# ToneGeneratorSMD_V2.net
KiCad netlist of a schematic drawn in EAGLE
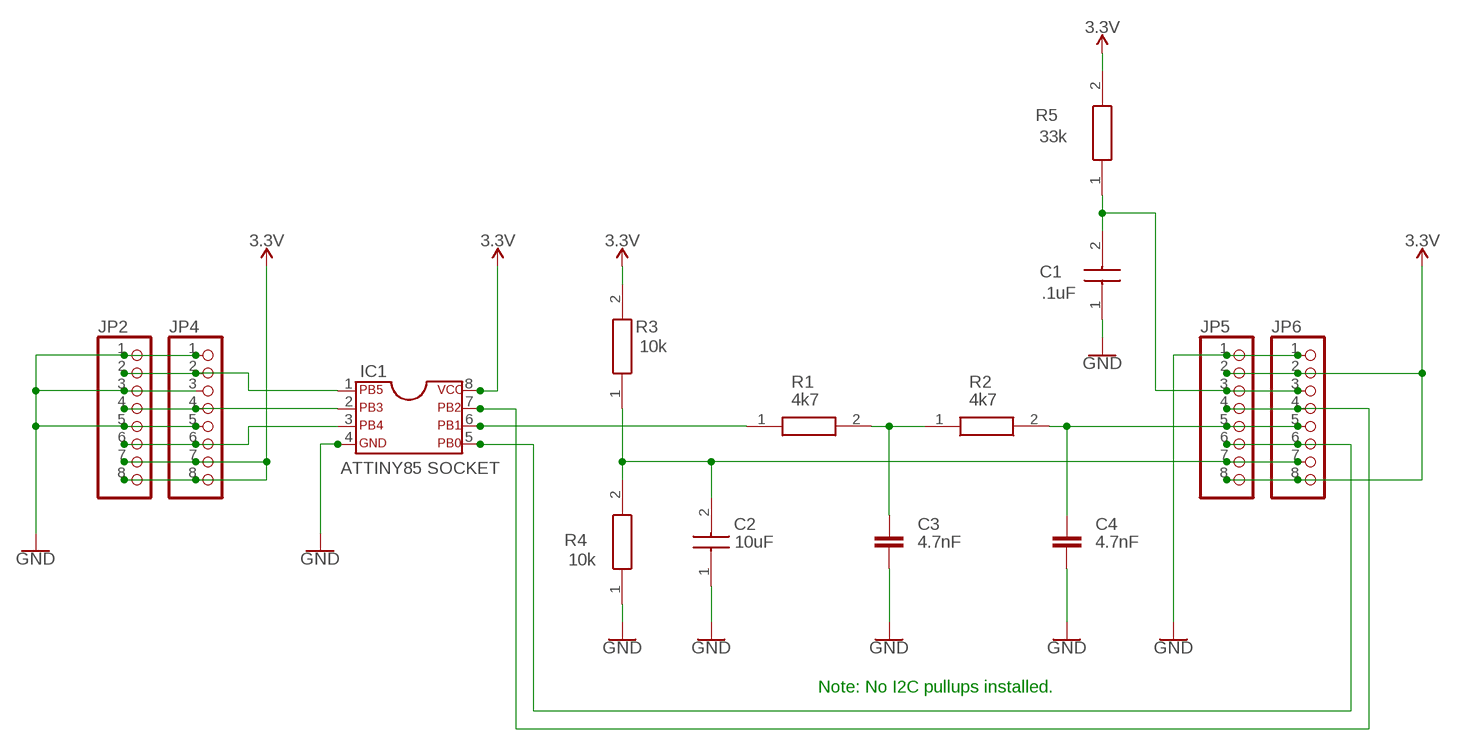
[diagram p0: schematic, sheet 1]

(export (version "E")
  (design (tool "Eeschema 10.0.6"))
  (components
    (comp (ref "C1")
      (value ".1uF")
      (footprint "eagle-import:CAPC2012X90N")
      (fields
        (field (name "MANUFACTURER_PART_NUMBER") "885012207098")
        (field (name "MOUSER_PART_NUMBER") "710-885012207098")
      )
      (libsource (lib "eagle-import") (part "885012207098"))
    )
    (comp (ref "C2")
      (value "10uF")
      (footprint "eagle-import:CAPC2012X145N")
      (fields
        (field (name "MANUFACTURER_PART_NUMBER") "GRM21BR61E106MA73L")
        (field (name "MOUSER_PART_NUMBER") "81-GRM21BR61E106MA3L")
      )
      (libsource (lib "eagle-import") (part "GRM21BR61E106MA73L"))
    )
    (comp (ref "C3")
      (value "4.7nF")
      (footprint "eagle-import:C0805")
      (libsource (lib "eagle-import") (part "C-EUC0805"))
    )
    (comp (ref "C4")
      (value "4.7nF")
      (footprint "eagle-import:C0805")
      (libsource (lib "eagle-import") (part "C-EUC0805"))
    )
    (comp (ref "IC1")
      (value "ATTINY85 SOCKET")
      (footprint "eagle-import:DIL08ATTINY85")
      (libsource (lib "eagle-import") (part "DIL8ATTINY85"))
    )
    (comp (ref "JP2")
      (value "PINHD-1X8")
      (footprint "eagle-import:1X08")
      (libsource (lib "eagle-import") (part "PINHD-1X8"))
    )
    (comp (ref "JP4")
      (value "PINHD-1X8")
      (footprint "eagle-import:1X08")
      (libsource (lib "eagle-import") (part "PINHD-1X8"))
    )
    (comp (ref "JP5")
      (value "PINHD-1X8")
      (footprint "eagle-import:1X08")
      (libsource (lib "eagle-import") (part "PINHD-1X8"))
    )
    (comp (ref "JP6")
      (value "PINHD-1X8")
      (footprint "eagle-import:1X08")
      (libsource (lib "eagle-import") (part "PINHD-1X8"))
    )
    (comp (ref "R1")
      (value "4k7")
      (footprint "eagle-import:RESC2013X65N")
      (fields
        (field (name "MANUFACTURER_PART_NUMBER") "ERJ-6GEYJ472V")
        (field (name "MOUSER_PART_NUMBER") "667-ERJ-6GEYJ472V")
      )
      (libsource (lib "eagle-import") (part "ERJ-6GEYJ472V"))
    )
    (comp (ref "R2")
      (value "4k7")
      (footprint "eagle-import:RESC2013X65N")
      (fields
        (field (name "MANUFACTURER_PART_NUMBER") "ERJ-6GEYJ472V")
        (field (name "MOUSER_PART_NUMBER") "667-ERJ-6GEYJ472V")
      )
      (libsource (lib "eagle-import") (part "ERJ-6GEYJ472V"))
    )
    (comp (ref "R3")
      (value "10k")
      (footprint "eagle-import:RESC2013X65N")
      (fields
        (field (name "MANUFACTURER_PART_NUMBER") "ERJ-6GEYJ472V")
        (field (name "MOUSER_PART_NUMBER") "667-ERJ-6GEYJ472V")
      )
      (libsource (lib "eagle-import") (part "ERJ-6GEYJ472V"))
    )
    (comp (ref "R4")
      (value "10k")
      (footprint "eagle-import:RESC2013X65N")
      (fields
        (field (name "MANUFACTURER_PART_NUMBER") "ERJ-6GEYJ472V")
        (field (name "MOUSER_PART_NUMBER") "667-ERJ-6GEYJ472V")
      )
      (libsource (lib "eagle-import") (part "ERJ-6GEYJ472V"))
    )
    (comp (ref "R5")
      (value "33k")
      (footprint "eagle-import:RESC2013X65N")
      (fields
        (field (name "MANUFACTURER_PART_NUMBER") "ERJ-6GEYJ472V")
        (field (name "MOUSER_PART_NUMBER") "667-ERJ-6GEYJ472V")
      )
      (libsource (lib "eagle-import") (part "ERJ-6GEYJ472V"))
    )
  )
  (nets
    (net (code "1") (name "3.3V") (class "Default")
      (node (ref "IC1") (pin "8") (pinfunction "8_8") (pintype "passive"))
      (node (ref "JP2") (pin "7") (pinfunction "7_7") (pintype "passive"))
      (node (ref "JP2") (pin "8") (pinfunction "8_8") (pintype "passive"))
      (node (ref "JP4") (pin "7") (pinfunction "7_7") (pintype "passive"))
      (node (ref "JP4") (pin "8") (pinfunction "8_8") (pintype "passive"))
      (node (ref "JP5") (pin "2") (pinfunction "2_2") (pintype "passive"))
      (node (ref "JP5") (pin "8") (pinfunction "8_8") (pintype "passive"))
      (node (ref "JP6") (pin "2") (pinfunction "2_2") (pintype "passive"))
      (node (ref "JP6") (pin "8") (pinfunction "8_8") (pintype "passive"))
      (node (ref "R3") (pin "2") (pinfunction "R2_2") (pintype "bidirectional"))
      (node (ref "R5") (pin "2") (pinfunction "R2_2") (pintype "bidirectional"))
    )
    (net (code "2") (name "GND") (class "Default")
      (node (ref "C1") (pin "1") (pinfunction "1_1") (pintype "bidirectional"))
      (node (ref "C2") (pin "1") (pinfunction "1_1") (pintype "bidirectional"))
      (node (ref "C3") (pin "2") (pinfunction "2_2") (pintype "passive"))
      (node (ref "C4") (pin "2") (pinfunction "2_2") (pintype "passive"))
      (node (ref "IC1") (pin "4") (pinfunction "4_4") (pintype "passive"))
      (node (ref "JP2") (pin "1") (pinfunction "1_1") (pintype "passive"))
      (node (ref "JP2") (pin "3") (pinfunction "3_3") (pintype "passive"))
      (node (ref "JP2") (pin "5") (pinfunction "5_5") (pintype "passive"))
      (node (ref "JP4") (pin "1") (pinfunction "1_1") (pintype "passive"))
      (node (ref "JP4") (pin "3") (pinfunction "3_3") (pintype "passive"))
      (node (ref "JP4") (pin "5") (pinfunction "5_5") (pintype "passive"))
      (node (ref "JP5") (pin "1") (pinfunction "1_1") (pintype "passive"))
      (node (ref "JP6") (pin "1") (pinfunction "1_1") (pintype "passive"))
      (node (ref "R4") (pin "1") (pinfunction "R1_1") (pintype "bidirectional"))
    )
    (net (code "3") (name "Net-(IC1-Pad1)") (class "Default")
      (node (ref "IC1") (pin "1") (pinfunction "1_1") (pintype "passive"))
      (node (ref "JP2") (pin "2") (pinfunction "2_2") (pintype "passive"))
      (node (ref "JP4") (pin "2") (pinfunction "2_2") (pintype "passive"))
    )
    (net (code "4") (name "Net-(IC1-Pad2)") (class "Default")
      (node (ref "IC1") (pin "2") (pinfunction "2_2") (pintype "passive"))
      (node (ref "JP2") (pin "4") (pinfunction "4_4") (pintype "passive"))
      (node (ref "JP4") (pin "4") (pinfunction "4_4") (pintype "passive"))
    )
    (net (code "5") (name "Net-(IC1-Pad3)") (class "Default")
      (node (ref "IC1") (pin "3") (pinfunction "3_3") (pintype "passive"))
      (node (ref "JP2") (pin "6") (pinfunction "6_6") (pintype "passive"))
      (node (ref "JP4") (pin "6") (pinfunction "6_6") (pintype "passive"))
    )
    (net (code "6") (name "Net-(IC1-Pad5)") (class "Default")
      (node (ref "IC1") (pin "5") (pinfunction "5_5") (pintype "passive"))
      (node (ref "JP5") (pin "6") (pinfunction "6_6") (pintype "passive"))
      (node (ref "JP6") (pin "6") (pinfunction "6_6") (pintype "passive"))
    )
    (net (code "7") (name "Net-(IC1-Pad7)") (class "Default")
      (node (ref "IC1") (pin "7") (pinfunction "7_7") (pintype "passive"))
      (node (ref "JP5") (pin "4") (pinfunction "4_4") (pintype "passive"))
      (node (ref "JP6") (pin "4") (pinfunction "4_4") (pintype "passive"))
    )
    (net (code "8") (name "Net-(R1-R1)") (class "Default")
      (node (ref "IC1") (pin "6") (pinfunction "6_6") (pintype "passive"))
      (node (ref "R1") (pin "1") (pinfunction "R1_1") (pintype "bidirectional"))
    )
    (net (code "9") (name "Net-(R1-R2)") (class "Default")
      (node (ref "C3") (pin "1") (pinfunction "1_1") (pintype "passive"))
      (node (ref "R1") (pin "2") (pinfunction "R2_2") (pintype "bidirectional"))
      (node (ref "R2") (pin "1") (pinfunction "R1_1") (pintype "bidirectional"))
    )
    (net (code "10") (name "Net-(R2-R2)") (class "Default")
      (node (ref "C4") (pin "1") (pinfunction "1_1") (pintype "passive"))
      (node (ref "JP5") (pin "5") (pinfunction "5_5") (pintype "passive"))
      (node (ref "JP6") (pin "5") (pinfunction "5_5") (pintype "passive"))
      (node (ref "R2") (pin "2") (pinfunction "R2_2") (pintype "bidirectional"))
    )
    (net (code "11") (name "Net-(R3-R1)") (class "Default")
      (node (ref "C2") (pin "2") (pinfunction "2_2") (pintype "bidirectional"))
      (node (ref "JP5") (pin "7") (pinfunction "7_7") (pintype "passive"))
      (node (ref "JP6") (pin "7") (pinfunction "7_7") (pintype "passive"))
      (node (ref "R3") (pin "1") (pinfunction "R1_1") (pintype "bidirectional"))
      (node (ref "R4") (pin "2") (pinfunction "R2_2") (pintype "bidirectional"))
    )
    (net (code "12") (name "Net-(R5-R1)") (class "Default")
      (node (ref "C1") (pin "2") (pinfunction "2_2") (pintype "bidirectional"))
      (node (ref "JP5") (pin "3") (pinfunction "3_3") (pintype "passive"))
      (node (ref "JP6") (pin "3") (pinfunction "3_3") (pintype "passive"))
      (node (ref "R5") (pin "1") (pinfunction "R1_1") (pintype "bidirectional"))
    )
  )
)
